# 202_9axisRev010100.net
KiCad netlist of a schematic drawn in EAGLE
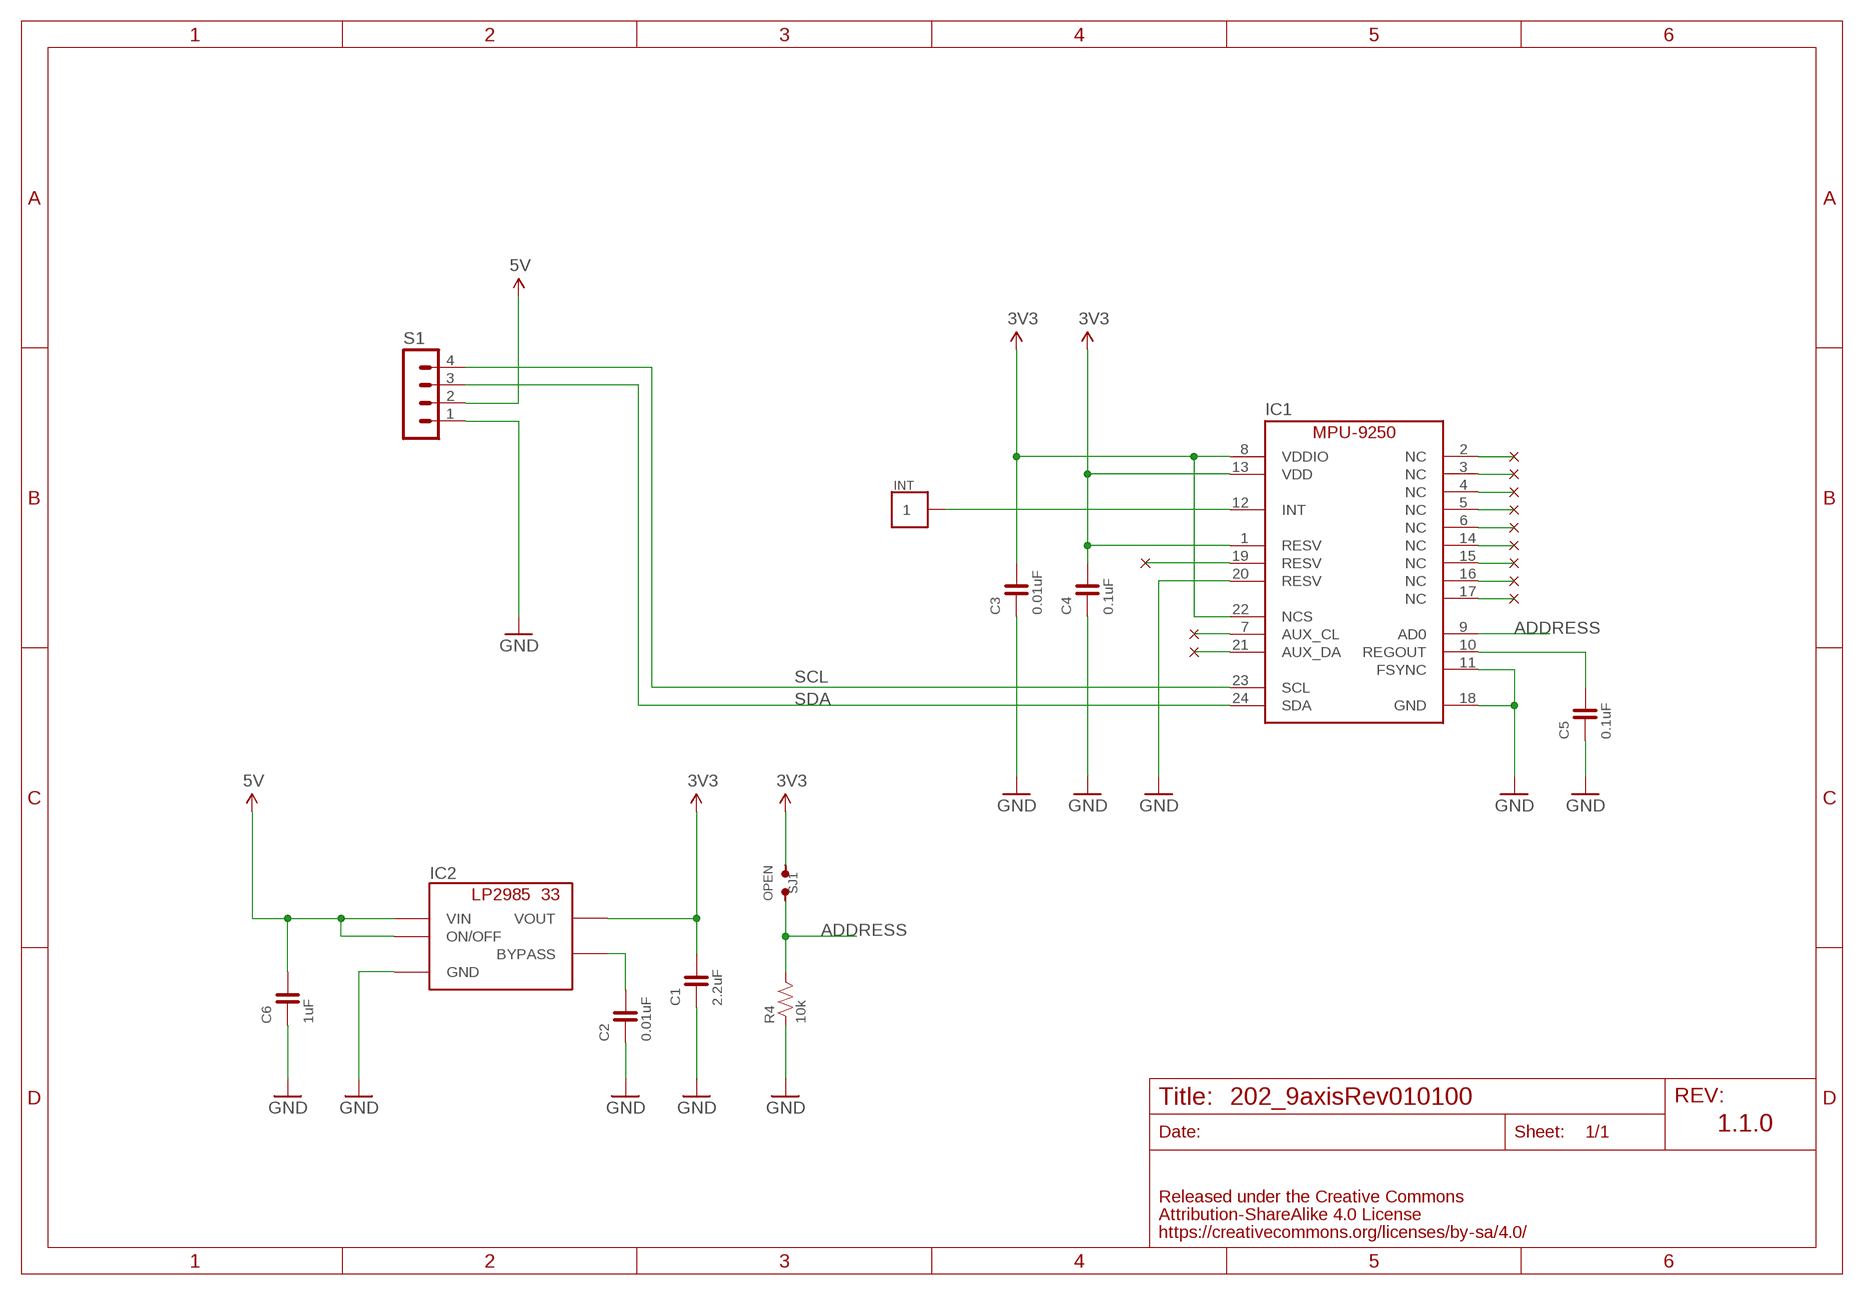
[diagram p0: schematic, sheet 1]

(export (version "E")
  (design (tool "Eeschema 10.0.6"))
  (components
    (comp (ref "C1")
      (value "2.2uF")
      (footprint "eagle-import:0603")
      (libsource (lib "eagle-import") (part "CAPACITOR-0603"))
    )
    (comp (ref "C2")
      (value "0.01uF")
      (footprint "eagle-import:0603")
      (libsource (lib "eagle-import") (part "CAPACITOR-0603"))
    )
    (comp (ref "C3")
      (value "0.01uF")
      (footprint "eagle-import:0603")
      (libsource (lib "eagle-import") (part "CAPACITOR-0603"))
    )
    (comp (ref "C4")
      (value "0.1uF")
      (footprint "eagle-import:0603")
      (libsource (lib "eagle-import") (part "CAPACITOR-0603"))
    )
    (comp (ref "C5")
      (value "0.1uF")
      (footprint "eagle-import:0603")
      (libsource (lib "eagle-import") (part "CAPACITOR-0603"))
    )
    (comp (ref "C6")
      (value "1uF")
      (footprint "eagle-import:0603")
      (libsource (lib "eagle-import") (part "CAPACITOR-0603"))
    )
    (comp (ref "IC1")
      (value "IS-MPU9250")
      (footprint "eagle-import:INVENSENSE-MPU9250")
      (libsource (lib "eagle-import") (part "IS-MPU9250"))
    )
    (comp (ref "IC2")
      (value "LP2985-33DBV")
      (footprint "eagle-import:SOT-23-5")
      (libsource (lib "eagle-import") (part "LP2985-33DBV"))
    )
    (comp (ref "INT")
      (value "PIN_1X1")
      (footprint "eagle-import:PIN_1X1")
      (libsource (lib "eagle-import") (part "PIN_1X1"))
    )
    (comp (ref "R4")
      (value "10k")
      (footprint "eagle-import:0603")
      (libsource (lib "eagle-import") (part "RESISTOR-0603"))
    )
    (comp (ref "S1")
      (value "MA04-1")
      (footprint "eagle-import:MA04-1")
      (libsource (lib "eagle-import") (part "MA04-1"))
    )
    (comp (ref "SJ1")
      (value "OPEN")
      (footprint "eagle-import:SMD-JUMPER-2-OPEN")
      (libsource (lib "eagle-import") (part "SMD-JUMPER-2-OPEN"))
    )
  )
  (nets
    (net (code "1") (name "/ADDRESS") (class "Default")
      (node (ref "IC1") (pin "9") (pinfunction "AD0_9") (pintype "bidirectional"))
      (node (ref "R4") (pin "2") (pinfunction "2_2") (pintype "bidirectional"))
      (node (ref "SJ1") (pin "2") (pinfunction "2_2") (pintype "passive"))
    )
    (net (code "2") (name "/SCL") (class "Default")
      (node (ref "IC1") (pin "23") (pinfunction "SCL_23") (pintype "bidirectional"))
      (node (ref "S1") (pin "4") (pinfunction "4_4") (pintype "passive"))
    )
    (net (code "3") (name "/SDA") (class "Default")
      (node (ref "IC1") (pin "24") (pinfunction "SDA_24") (pintype "bidirectional"))
      (node (ref "S1") (pin "3") (pinfunction "3_3") (pintype "passive"))
    )
    (net (code "4") (name "3V3") (class "Default")
      (node (ref "C1") (pin "2") (pinfunction "2_2") (pintype "passive"))
      (node (ref "C3") (pin "2") (pinfunction "2_2") (pintype "passive"))
      (node (ref "C4") (pin "2") (pinfunction "2_2") (pintype "passive"))
      (node (ref "IC1") (pin "1") (pinfunction "RESV_1") (pintype "bidirectional"))
      (node (ref "IC1") (pin "13") (pinfunction "VDD_13") (pintype "bidirectional"))
      (node (ref "IC1") (pin "22") (pinfunction "NCS_22") (pintype "bidirectional"))
      (node (ref "IC1") (pin "8") (pinfunction "VDDIO_8") (pintype "bidirectional"))
      (node (ref "IC2") (pin "5") (pinfunction "VOUT_5") (pintype "output"))
      (node (ref "SJ1") (pin "1") (pinfunction "1_1") (pintype "passive"))
    )
    (net (code "5") (name "5V") (class "Default")
      (node (ref "C6") (pin "2") (pinfunction "2_2") (pintype "passive"))
      (node (ref "IC2") (pin "1") (pinfunction "VIN_1") (pintype "input"))
      (node (ref "IC2") (pin "3") (pinfunction "ON/OFF_3") (pintype "input"))
      (node (ref "S1") (pin "2") (pinfunction "2_2") (pintype "passive"))
    )
    (net (code "6") (name "GND") (class "Default")
      (node (ref "C1") (pin "1") (pinfunction "1_1") (pintype "passive"))
      (node (ref "C2") (pin "1") (pinfunction "1_1") (pintype "passive"))
      (node (ref "C3") (pin "1") (pinfunction "1_1") (pintype "passive"))
      (node (ref "C4") (pin "1") (pinfunction "1_1") (pintype "passive"))
      (node (ref "C5") (pin "1") (pinfunction "1_1") (pintype "passive"))
      (node (ref "C6") (pin "1") (pinfunction "1_1") (pintype "passive"))
      (node (ref "IC1") (pin "11") (pinfunction "FSYNC_11") (pintype "bidirectional"))
      (node (ref "IC1") (pin "18") (pinfunction "GND_18") (pintype "bidirectional"))
      (node (ref "IC1") (pin "20") (pinfunction "RESV_20") (pintype "bidirectional"))
      (node (ref "IC2") (pin "2") (pinfunction "GND_2") (pintype "power_in"))
      (node (ref "R4") (pin "1") (pinfunction "1_1") (pintype "bidirectional"))
      (node (ref "S1") (pin "1") (pinfunction "1_1") (pintype "passive"))
    )
    (net (code "7") (name "Net-(IC1-INT)") (class "Default")
      (node (ref "IC1") (pin "12") (pinfunction "INT_12") (pintype "bidirectional"))
      (node (ref "INT") (pin "1") (pinfunction "1_1") (pintype "bidirectional"))
    )
    (net (code "8") (name "Net-(IC1-REGOUT)") (class "Default")
      (node (ref "C5") (pin "2") (pinfunction "2_2") (pintype "passive"))
      (node (ref "IC1") (pin "10") (pinfunction "REGOUT_10") (pintype "bidirectional"))
    )
    (net (code "9") (name "Net-(IC2-BYPASS)") (class "Default")
      (node (ref "C2") (pin "2") (pinfunction "2_2") (pintype "passive"))
      (node (ref "IC2") (pin "4") (pinfunction "BYPASS_4") (pintype "bidirectional"))
    )
    (net (code "10") (name "unconnected-(IC1-AUX_CL-Pad7)") (class "Default")
      (node (ref "IC1") (pin "7") (pinfunction "AUX_CL_7") (pintype "bidirectional"))
    )
    (net (code "11") (name "unconnected-(IC1-AUX_DA-Pad21)") (class "Default")
      (node (ref "IC1") (pin "21") (pinfunction "AUX_DA_21") (pintype "bidirectional"))
    )
    (net (code "12") (name "unconnected-(IC1-NC-Pad2)") (class "Default")
      (node (ref "IC1") (pin "2") (pinfunction "NC_2") (pintype "bidirectional"))
    )
    (net (code "13") (name "unconnected-(IC1-NC-Pad3)") (class "Default")
      (node (ref "IC1") (pin "3") (pinfunction "NC_3") (pintype "bidirectional"))
    )
    (net (code "14") (name "unconnected-(IC1-NC-Pad4)") (class "Default")
      (node (ref "IC1") (pin "4") (pinfunction "NC_4") (pintype "bidirectional"))
    )
    (net (code "15") (name "unconnected-(IC1-NC-Pad5)") (class "Default")
      (node (ref "IC1") (pin "5") (pinfunction "NC_5") (pintype "bidirectional"))
    )
    (net (code "16") (name "unconnected-(IC1-NC-Pad6)") (class "Default")
      (node (ref "IC1") (pin "6") (pinfunction "NC_6") (pintype "bidirectional"))
    )
    (net (code "17") (name "unconnected-(IC1-NC-Pad14)") (class "Default")
      (node (ref "IC1") (pin "14") (pinfunction "NC_14") (pintype "bidirectional"))
    )
    (net (code "18") (name "unconnected-(IC1-NC-Pad15)") (class "Default")
      (node (ref "IC1") (pin "15") (pinfunction "NC_15") (pintype "bidirectional"))
    )
    (net (code "19") (name "unconnected-(IC1-NC-Pad16)") (class "Default")
      (node (ref "IC1") (pin "16") (pinfunction "NC_16") (pintype "bidirectional"))
    )
    (net (code "20") (name "unconnected-(IC1-NC-Pad17)") (class "Default")
      (node (ref "IC1") (pin "17") (pinfunction "NC_17") (pintype "bidirectional"))
    )
    (net (code "21") (name "unconnected-(IC1-RESV-Pad19)") (class "Default")
      (node (ref "IC1") (pin "19") (pinfunction "RESV_19") (pintype "bidirectional"))
    )
  )
)
